# Kernal64Cart.net
KiCad netlist of a schematic drawn in EAGLE
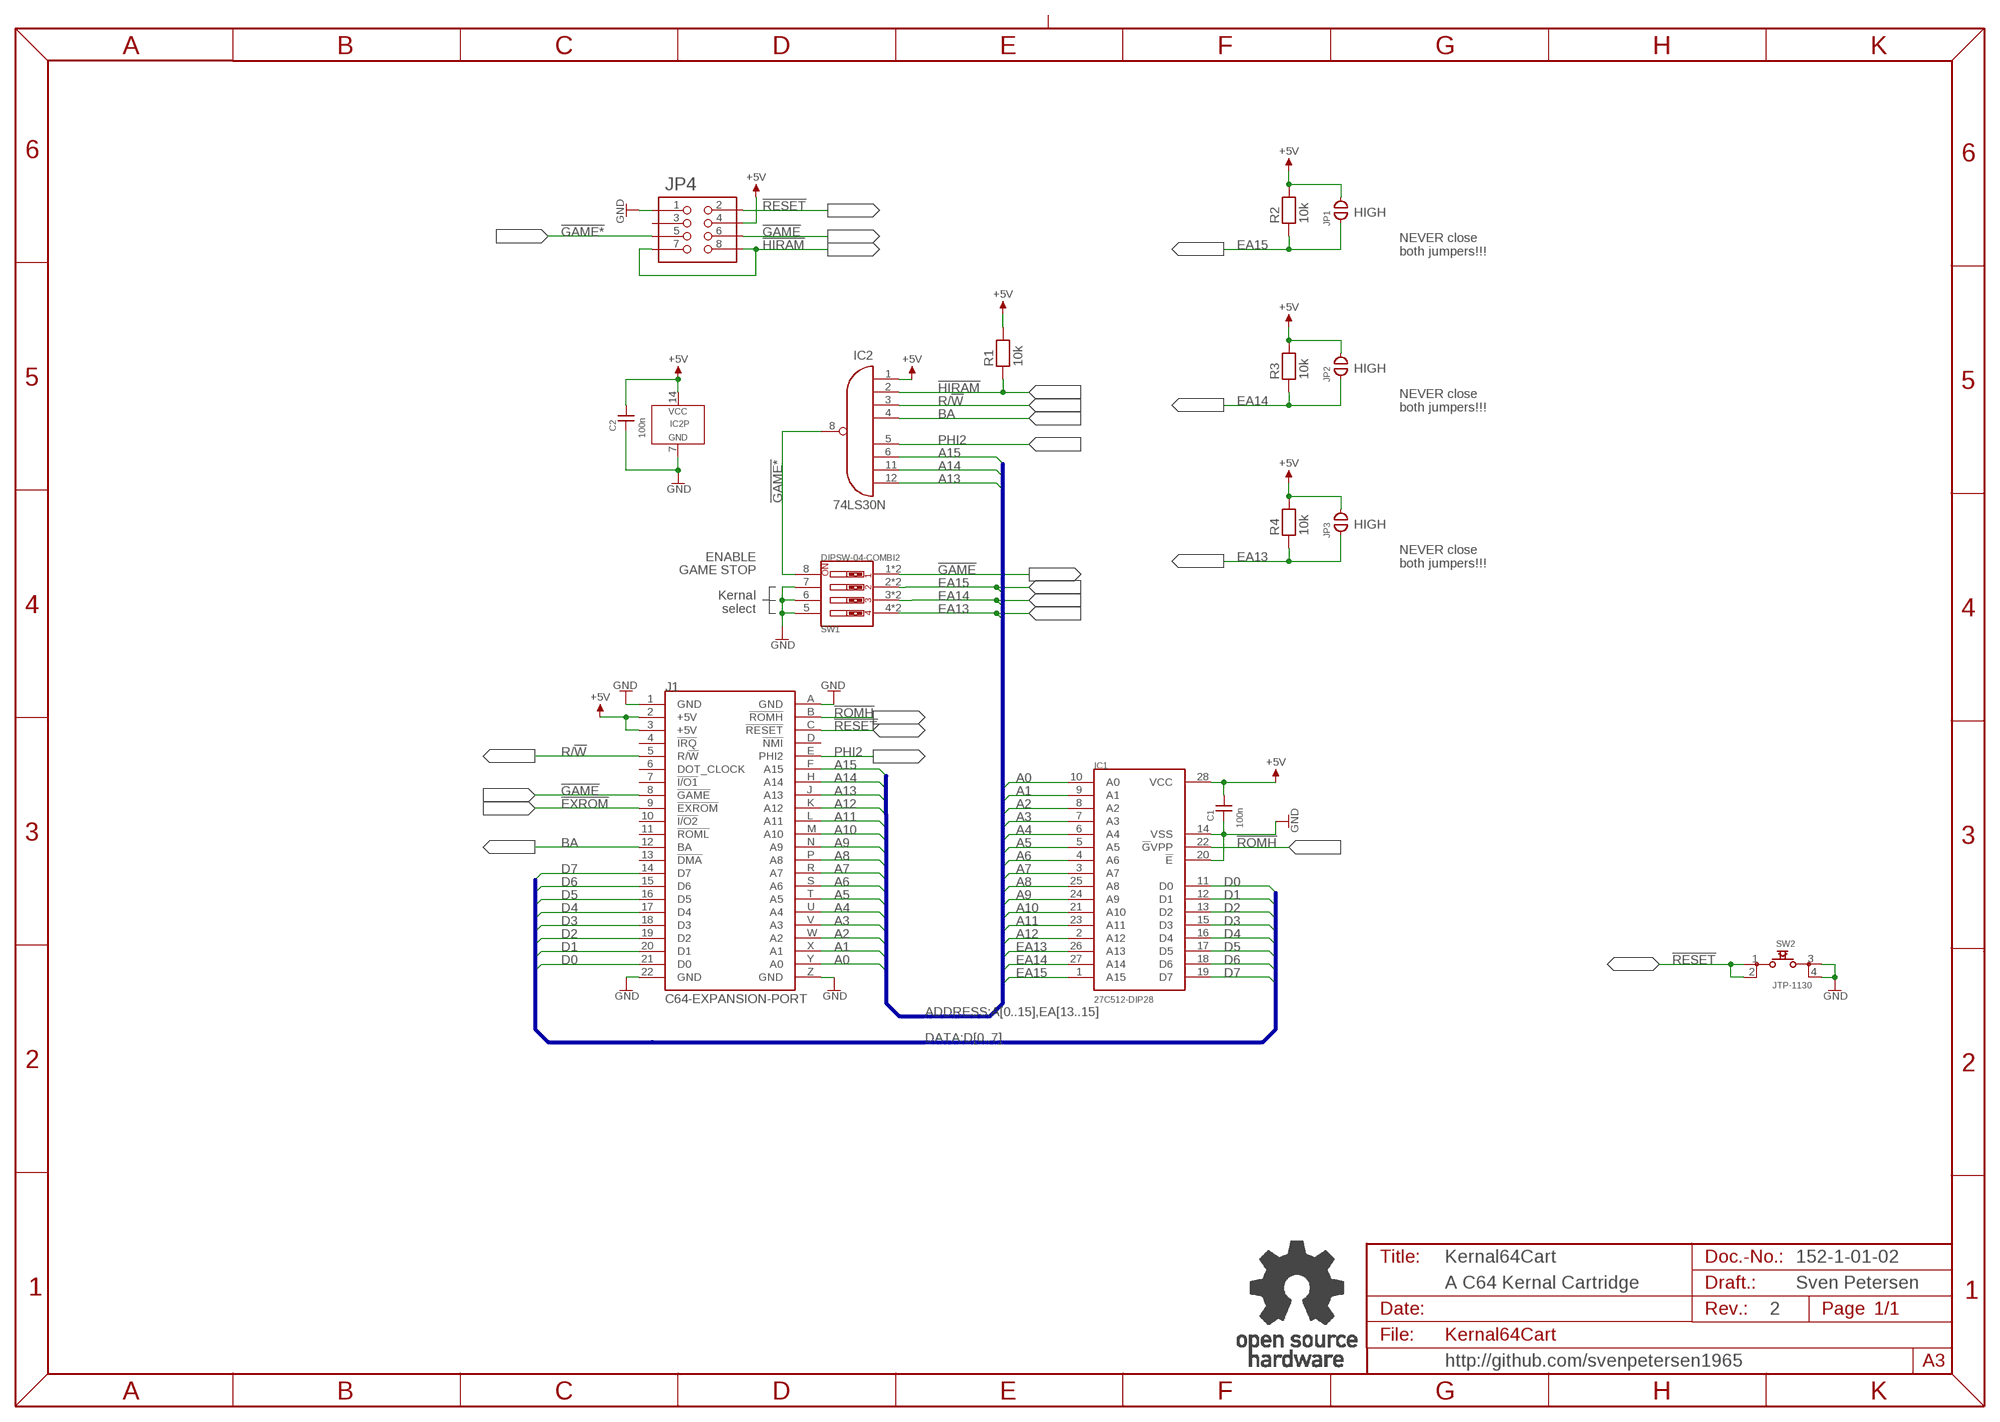
[diagram p0: schematic, sheet 1]

(export (version "E")
  (design (tool "Eeschema 10.0.6"))
  (components
    (comp (ref "C1")
      (value "100n")
      (footprint "eagle-import:C-2,5")
      (libsource (lib "eagle-import") (part "CAP01"))
    )
    (comp (ref "C2")
      (value "100n")
      (footprint "eagle-import:C-2,5")
      (libsource (lib "eagle-import") (part "CAP01"))
    )
    (comp (ref "IC1")
      (value "27C512-DIP28")
      (footprint "eagle-import:DIL28-6")
      (libsource (lib "eagle-import") (part "M27C512-DIP28"))
    )
    (comp (ref "IC2")
      (value "74LS30N")
      (footprint "eagle-import:DIL-14")
      (libsource (lib "eagle-import") (part "7430DIP"))
    )
    (comp (ref "J1")
      (value "C64-EXPANSION-PORT")
      (footprint "eagle-import:EXPANSIO_SQ")
      (libsource (lib "eagle-import") (part "C64-EXPANSIONPNARROW"))
    )
    (comp (ref "JP1")
      (value "OPEN")
      (footprint "eagle-import:CP_OP")
      (libsource (lib "eagle-import") (part "OPEN"))
    )
    (comp (ref "JP2")
      (value "OPEN")
      (footprint "eagle-import:CP_OP")
      (libsource (lib "eagle-import") (part "OPEN"))
    )
    (comp (ref "JP3")
      (value "OPEN")
      (footprint "eagle-import:CP_OP")
      (libsource (lib "eagle-import") (part "OPEN"))
    )
    (comp (ref "JP4")
      (value "PINHD-2X490°/MPE_088")
      (footprint "eagle-import:2X04_90_SERIES_088")
      (libsource (lib "eagle-import") (part "PINHD-2X490°/MPE_088"))
    )
    (comp (ref "R1")
      (value "10k")
      (footprint "eagle-import:R-10")
      (libsource (lib "eagle-import") (part "RES04"))
    )
    (comp (ref "R2")
      (value "10k")
      (footprint "eagle-import:R-10")
      (libsource (lib "eagle-import") (part "RES04"))
    )
    (comp (ref "R3")
      (value "10k")
      (footprint "eagle-import:R-10")
      (libsource (lib "eagle-import") (part "RES04"))
    )
    (comp (ref "R4")
      (value "10k")
      (footprint "eagle-import:R-10")
      (libsource (lib "eagle-import") (part "RES04"))
    )
    (comp (ref "SW1")
      (value "DIPSW-04-COMBI2")
      (footprint "eagle-import:DIPSW-04V-COMBI2")
      (libsource (lib "eagle-import") (part "DIPSW-04-COMBI2"))
    )
    (comp (ref "SW2")
      (value "JTP-1130")
      (footprint "eagle-import:JTP-1130")
      (libsource (lib "eagle-import") (part "JTP-1130"))
    )
    (comp (ref "U$50")
      (value "OPEN_SOURCE_HW")
      (footprint "eagle-import:OPENHW")
      (libsource (lib "eagle-import") (part "OPEN_SOURCE_HW"))
    )
  )
  (nets
    (net (code "9") (name "+5V") (class "Default")
      (node (ref "C1") (pin "2") (pinfunction "2_2") (pintype "passive"))
      (node (ref "C2") (pin "2") (pinfunction "2_2") (pintype "passive"))
      (node (ref "IC1") (pin "28") (pinfunction "VCC_28") (pintype "power_in"))
      (node (ref "IC2") (pin "1") (pinfunction "I0_1") (pintype "input"))
      (node (ref "IC2") (pin "14") (pinfunction "VCC_14") (pintype "bidirectional"))
      (node (ref "J1") (pin "2") (pinfunction "+5V_2") (pintype "power_in"))
      (node (ref "J1") (pin "3") (pinfunction "+5V_3") (pintype "power_in"))
      (node (ref "JP1") (pin "2") (pinfunction "2_2") (pintype "passive"))
      (node (ref "JP2") (pin "2") (pinfunction "2_2") (pintype "passive"))
      (node (ref "JP3") (pin "2") (pinfunction "2_2") (pintype "passive"))
      (node (ref "JP4") (pin "4") (pinfunction "4_4") (pintype "passive"))
      (node (ref "R1") (pin "2") (pinfunction "2_2") (pintype "passive"))
      (node (ref "R2") (pin "2") (pinfunction "2_2") (pintype "passive"))
      (node (ref "R3") (pin "2") (pinfunction "2_2") (pintype "passive"))
      (node (ref "R4") (pin "2") (pinfunction "2_2") (pintype "passive"))
    )
    (net (code "10") (name "/A0") (class "Default")
      (node (ref "IC1") (pin "10") (pinfunction "A0_10") (pintype "input"))
      (node (ref "J1") (pin "Y") (pinfunction "A0_Y") (pintype "bidirectional"))
    )
    (net (code "11") (name "/A1") (class "Default")
      (node (ref "IC1") (pin "9") (pinfunction "A1_9") (pintype "input"))
      (node (ref "J1") (pin "X") (pinfunction "A1_X") (pintype "bidirectional"))
    )
    (net (code "12") (name "/A2") (class "Default")
      (node (ref "IC1") (pin "8") (pinfunction "A2_8") (pintype "input"))
      (node (ref "J1") (pin "W") (pinfunction "A2_W") (pintype "bidirectional"))
    )
    (net (code "13") (name "/A3") (class "Default")
      (node (ref "IC1") (pin "7") (pinfunction "A3_7") (pintype "input"))
      (node (ref "J1") (pin "V") (pinfunction "A3_V") (pintype "bidirectional"))
    )
    (net (code "14") (name "/A4") (class "Default")
      (node (ref "IC1") (pin "6") (pinfunction "A4_6") (pintype "input"))
      (node (ref "J1") (pin "U") (pinfunction "A4_U") (pintype "bidirectional"))
    )
    (net (code "15") (name "/A5") (class "Default")
      (node (ref "IC1") (pin "5") (pinfunction "A5_5") (pintype "input"))
      (node (ref "J1") (pin "T") (pinfunction "A5_T") (pintype "bidirectional"))
    )
    (net (code "16") (name "/A6") (class "Default")
      (node (ref "IC1") (pin "4") (pinfunction "A6_4") (pintype "input"))
      (node (ref "J1") (pin "S") (pinfunction "A6_S") (pintype "bidirectional"))
    )
    (net (code "17") (name "/A7") (class "Default")
      (node (ref "IC1") (pin "3") (pinfunction "A7_3") (pintype "input"))
      (node (ref "J1") (pin "R") (pinfunction "A7_R") (pintype "bidirectional"))
    )
    (net (code "18") (name "/A8") (class "Default")
      (node (ref "IC1") (pin "25") (pinfunction "A8_25") (pintype "input"))
      (node (ref "J1") (pin "P") (pinfunction "A8_P") (pintype "bidirectional"))
    )
    (net (code "19") (name "/A9") (class "Default")
      (node (ref "IC1") (pin "24") (pinfunction "A9_24") (pintype "input"))
      (node (ref "J1") (pin "N") (pinfunction "A9_N") (pintype "bidirectional"))
    )
    (net (code "20") (name "/A10") (class "Default")
      (node (ref "IC1") (pin "21") (pinfunction "A10_21") (pintype "input"))
      (node (ref "J1") (pin "M") (pinfunction "A10_M") (pintype "bidirectional"))
    )
    (net (code "21") (name "/A11") (class "Default")
      (node (ref "IC1") (pin "23") (pinfunction "A11_23") (pintype "input"))
      (node (ref "J1") (pin "L") (pinfunction "A11_L") (pintype "bidirectional"))
    )
    (net (code "22") (name "/A12") (class "Default")
      (node (ref "IC1") (pin "2") (pinfunction "A12_2") (pintype "input"))
      (node (ref "J1") (pin "K") (pinfunction "A12_K") (pintype "bidirectional"))
    )
    (net (code "23") (name "/A13") (class "Default")
      (node (ref "IC2") (pin "12") (pinfunction "I7_12") (pintype "input"))
      (node (ref "J1") (pin "J") (pinfunction "A13_J") (pintype "bidirectional"))
    )
    (net (code "24") (name "/A14") (class "Default")
      (node (ref "IC2") (pin "11") (pinfunction "I6_11") (pintype "input"))
      (node (ref "J1") (pin "H") (pinfunction "A14_H") (pintype "bidirectional"))
    )
    (net (code "25") (name "/A15") (class "Default")
      (node (ref "IC2") (pin "6") (pinfunction "I5_6") (pintype "input"))
      (node (ref "J1") (pin "F") (pinfunction "A15_F") (pintype "bidirectional"))
    )
    (net (code "26") (name "/BA") (class "Default")
      (node (ref "IC2") (pin "4") (pinfunction "I3_4") (pintype "input"))
      (node (ref "J1") (pin "12") (pinfunction "BA_12") (pintype "output"))
    )
    (net (code "27") (name "/D0") (class "Default")
      (node (ref "IC1") (pin "11") (pinfunction "D0_11") (pintype "bidirectional"))
      (node (ref "J1") (pin "21") (pinfunction "D0_21") (pintype "bidirectional"))
    )
    (net (code "28") (name "/D1") (class "Default")
      (node (ref "IC1") (pin "12") (pinfunction "D1_12") (pintype "bidirectional"))
      (node (ref "J1") (pin "20") (pinfunction "D1_20") (pintype "bidirectional"))
    )
    (net (code "29") (name "/D2") (class "Default")
      (node (ref "IC1") (pin "13") (pinfunction "D2_13") (pintype "bidirectional"))
      (node (ref "J1") (pin "19") (pinfunction "D2_19") (pintype "bidirectional"))
    )
    (net (code "30") (name "/D3") (class "Default")
      (node (ref "IC1") (pin "15") (pinfunction "D3_15") (pintype "bidirectional"))
      (node (ref "J1") (pin "18") (pinfunction "D3_18") (pintype "bidirectional"))
    )
    (net (code "31") (name "/D4") (class "Default")
      (node (ref "IC1") (pin "16") (pinfunction "D4_16") (pintype "bidirectional"))
      (node (ref "J1") (pin "17") (pinfunction "D4_17") (pintype "bidirectional"))
    )
    (net (code "32") (name "/D5") (class "Default")
      (node (ref "IC1") (pin "17") (pinfunction "D5_17") (pintype "bidirectional"))
      (node (ref "J1") (pin "16") (pinfunction "D5_16") (pintype "bidirectional"))
    )
    (net (code "33") (name "/D6") (class "Default")
      (node (ref "IC1") (pin "18") (pinfunction "D6_18") (pintype "bidirectional"))
      (node (ref "J1") (pin "15") (pinfunction "D6_15") (pintype "bidirectional"))
    )
    (net (code "34") (name "/D7") (class "Default")
      (node (ref "IC1") (pin "19") (pinfunction "D7_19") (pintype "bidirectional"))
      (node (ref "J1") (pin "14") (pinfunction "D7_14") (pintype "bidirectional"))
    )
    (net (code "36") (name "/EA13") (class "Default")
      (node (ref "IC1") (pin "26") (pinfunction "A13_26") (pintype "input"))
      (node (ref "JP3") (pin "1") (pinfunction "1_1") (pintype "passive"))
      (node (ref "R4") (pin "1") (pinfunction "1_1") (pintype "passive"))
      (node (ref "SW1") (pin "4") (pinfunction "4_4") (pintype "passive"))
      (node (ref "SW1") (pin "4A") (pinfunction "4_4A") (pintype "passive"))
    )
    (net (code "37") (name "/EA14") (class "Default")
      (node (ref "IC1") (pin "27") (pinfunction "A14_27") (pintype "input"))
      (node (ref "JP2") (pin "1") (pinfunction "1_1") (pintype "passive"))
      (node (ref "R3") (pin "1") (pinfunction "1_1") (pintype "passive"))
      (node (ref "SW1") (pin "3") (pinfunction "3_3") (pintype "passive"))
      (node (ref "SW1") (pin "3A") (pinfunction "3_3A") (pintype "passive"))
    )
    (net (code "38") (name "/EA15") (class "Default")
      (node (ref "IC1") (pin "1") (pinfunction "A15_1") (pintype "input"))
      (node (ref "JP1") (pin "1") (pinfunction "1_1") (pintype "passive"))
      (node (ref "R2") (pin "1") (pinfunction "1_1") (pintype "passive"))
      (node (ref "SW1") (pin "2") (pinfunction "2_2") (pintype "passive"))
      (node (ref "SW1") (pin "2A") (pinfunction "2_2A") (pintype "passive"))
    )
    (net (code "39") (name "/PHI2") (class "Default")
      (node (ref "IC2") (pin "5") (pinfunction "I4_5") (pintype "input"))
      (node (ref "J1") (pin "E") (pinfunction "PHI2_E") (pintype "output"))
    )
    (net (code "40") (name "/R{slash}~{W}") (class "Default")
      (node (ref "IC2") (pin "3") (pinfunction "I2_3") (pintype "input"))
      (node (ref "J1") (pin "5") (pinfunction "R/~{W}_5") (pintype "output"))
    )
    (net (code "42") (name "/~{EXROM}") (class "Default")
      (node (ref "J1") (pin "9") (pinfunction "~{EXROM}_9") (pintype "input"))
    )
    (net (code "43") (name "/~{GAME*}") (class "Default")
      (node (ref "IC2") (pin "8") (pinfunction "O_8") (pintype "output"))
      (node (ref "JP4") (pin "5") (pinfunction "5_5") (pintype "passive"))
      (node (ref "SW1") (pin "8") (pinfunction "8_8") (pintype "passive"))
    )
    (net (code "44") (name "/~{GAME}") (class "Default")
      (node (ref "J1") (pin "8") (pinfunction "~{GAME}_8") (pintype "input"))
      (node (ref "JP4") (pin "6") (pinfunction "6_6") (pintype "passive"))
      (node (ref "SW1") (pin "1") (pinfunction "1_1") (pintype "passive"))
      (node (ref "SW1") (pin "1A") (pinfunction "1_1A") (pintype "passive"))
    )
    (net (code "45") (name "/~{HIRAM}") (class "Default")
      (node (ref "IC2") (pin "2") (pinfunction "I1_2") (pintype "input"))
      (node (ref "JP4") (pin "7") (pinfunction "7_7") (pintype "passive"))
      (node (ref "JP4") (pin "8") (pinfunction "8_8") (pintype "passive"))
      (node (ref "R1") (pin "1") (pinfunction "1_1") (pintype "passive"))
    )
    (net (code "46") (name "/~{RESET}") (class "Default")
      (node (ref "J1") (pin "C") (pinfunction "~{RESET}_C") (pintype "open_collector"))
      (node (ref "JP4") (pin "2") (pinfunction "2_2") (pintype "passive"))
      (node (ref "SW2") (pin "1") (pinfunction "1_1") (pintype "passive"))
      (node (ref "SW2") (pin "2") (pinfunction "2_2") (pintype "passive"))
    )
    (net (code "47") (name "/~{ROMH}") (class "Default")
      (node (ref "IC1") (pin "22") (pinfunction "~{G}VPP_22") (pintype "input"))
      (node (ref "J1") (pin "B") (pinfunction "~{ROMH}_B") (pintype "output"))
    )
    (net (code "48") (name "GND") (class "Default")
      (node (ref "C1") (pin "1") (pinfunction "1_1") (pintype "passive"))
      (node (ref "C2") (pin "1") (pinfunction "1_1") (pintype "passive"))
      (node (ref "IC1") (pin "14") (pinfunction "VSS_14") (pintype "power_in"))
      (node (ref "IC1") (pin "20") (pinfunction "~{E}_20") (pintype "input"))
      (node (ref "IC2") (pin "7") (pinfunction "GND_7") (pintype "bidirectional"))
      (node (ref "J1") (pin "1") (pinfunction "GND_1") (pintype "power_in"))
      (node (ref "J1") (pin "22") (pinfunction "GND_22") (pintype "power_in"))
      (node (ref "J1") (pin "A") (pinfunction "GND_A") (pintype "power_in"))
      (node (ref "J1") (pin "Z") (pinfunction "GND_Z") (pintype "power_in"))
      (node (ref "JP4") (pin "1") (pinfunction "1_1") (pintype "passive"))
      (node (ref "SW1") (pin "5") (pinfunction "5_5") (pintype "passive"))
      (node (ref "SW1") (pin "6") (pinfunction "6_6") (pintype "passive"))
      (node (ref "SW1") (pin "7") (pinfunction "7_7") (pintype "passive"))
      (node (ref "SW2") (pin "3") (pinfunction "3_3") (pintype "passive"))
      (node (ref "SW2") (pin "4") (pinfunction "4_4") (pintype "passive"))
    )
    (net (code "49") (name "unconnected-(J1-DOT_CLOCK-Pad6)") (class "Default")
      (node (ref "J1") (pin "6") (pinfunction "DOT_CLOCK_6") (pintype "output"))
    )
    (net (code "50") (name "unconnected-(J1-~{DMA}-Pad13)") (class "Default")
      (node (ref "J1") (pin "13") (pinfunction "~{DMA}_13") (pintype "input"))
    )
    (net (code "51") (name "unconnected-(J1-~{IRQ}-Pad4)") (class "Default")
      (node (ref "J1") (pin "4") (pinfunction "~{IRQ}_4") (pintype "input"))
    )
    (net (code "52") (name "unconnected-(J1-~{I{slash}O1}-Pad7)") (class "Default")
      (node (ref "J1") (pin "7") (pinfunction "~{I/O1}_7") (pintype "output"))
    )
    (net (code "53") (name "unconnected-(J1-~{I{slash}O2}-Pad10)") (class "Default")
      (node (ref "J1") (pin "10") (pinfunction "~{I/O2}_10") (pintype "output"))
    )
    (net (code "54") (name "unconnected-(J1-~{NMI}-PadD)") (class "Default")
      (node (ref "J1") (pin "D") (pinfunction "~{NMI}_D") (pintype "input"))
    )
    (net (code "55") (name "unconnected-(J1-~{ROML}-Pad11)") (class "Default")
      (node (ref "J1") (pin "11") (pinfunction "~{ROML}_11") (pintype "output"))
    )
    (net (code "56") (name "unconnected-(JP4-Pad3)") (class "Default")
      (node (ref "JP4") (pin "3") (pinfunction "3_3") (pintype "passive"))
    )
  )
)
